# GoodBoy_V1_nRF9160dk_button_and_leds.net
KiCad netlist of a schematic drawn in Altium Designer
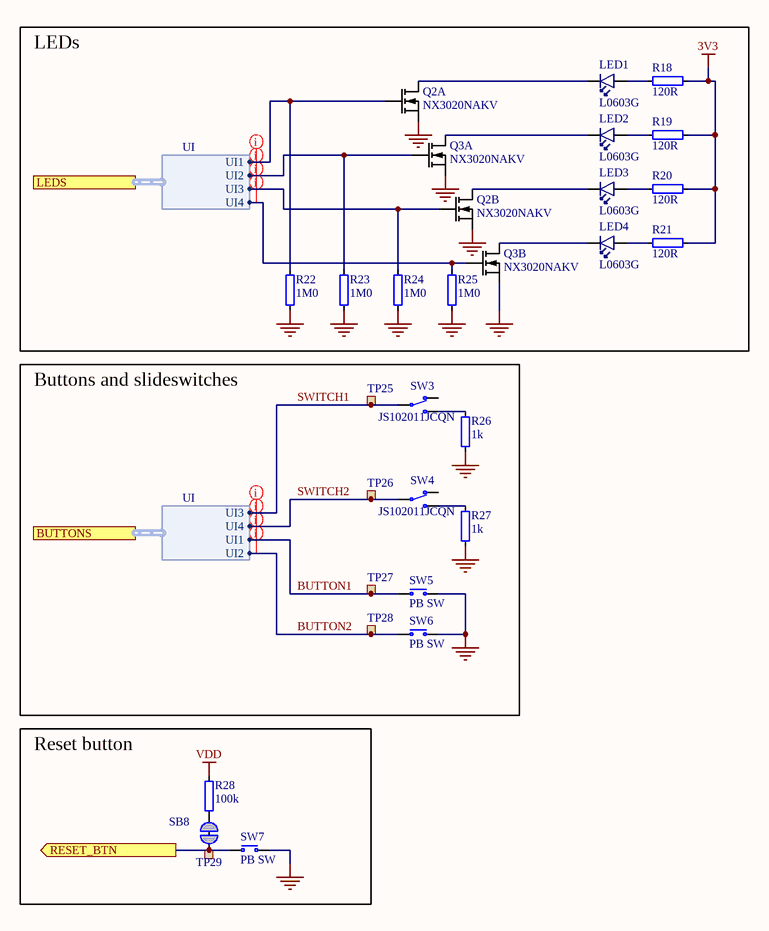
[diagram p0: GoodBoy_V1_nRF9160dk_button_and_leds.SchDoc]

(export (version "E")
  (design (tool "Eeschema 10.0.6"))
  (components
    (comp (ref "LED1")
      (value "L0603G")
      (footprint "LED_0603_G")
      (description "LED, Green, 0603, 570nm, Vf=1.7V, 2.24..5.6mcd, - 40 to +100°C")
      (fields
        (field (name "PART NUMBER") "LG L29K Smartled Green")
        (field (name "MANUFACTURER") "Osram")
        (field (name "PUBLISHER") "Nordic Semiconductor")
      )
      (libsource (lib "Nordic Discrete DB") (part "D{colon}LED"))
    )
    (comp (ref "LED2")
      (value "L0603G")
      (footprint "LED_0603_G")
      (description "LED, Green, 0603, 570nm, Vf=1.7V, 2.24..5.6mcd, - 40 to +100°C")
      (fields
        (field (name "PART NUMBER") "LG L29K Smartled Green")
        (field (name "MANUFACTURER") "Osram")
        (field (name "PUBLISHER") "Nordic Semiconductor")
      )
      (libsource (lib "Nordic Discrete DB") (part "D{colon}LED"))
    )
    (comp (ref "LED3")
      (value "L0603G")
      (footprint "LED_0603_G")
      (description "LED, Green, 0603, 570nm, Vf=1.7V, 2.24..5.6mcd, - 40 to +100°C")
      (fields
        (field (name "PART NUMBER") "LG L29K Smartled Green")
        (field (name "MANUFACTURER") "Osram")
        (field (name "PUBLISHER") "Nordic Semiconductor")
      )
      (libsource (lib "Nordic Discrete DB") (part "D{colon}LED"))
    )
    (comp (ref "LED4")
      (value "L0603G")
      (footprint "LED_0603_G")
      (description "LED, Green, 0603, 570nm, Vf=1.7V, 2.24..5.6mcd, - 40 to +100°C")
      (fields
        (field (name "PART NUMBER") "LG L29K Smartled Green")
        (field (name "MANUFACTURER") "Osram")
        (field (name "PUBLISHER") "Nordic Semiconductor")
      )
      (libsource (lib "Nordic Discrete DB") (part "D{colon}LED"))
    )
    (comp (ref "Q2")
      (value "NX3020NAKV")
      (footprint "NX3020NAKV")
      (description "MOSFET 2N-CH 30V 0.2A SOT666")
      (fields
        (field (name "MANUFACTURER") "Nexperia")
        (field (name "MANUFACTURER PART NUMBER") "NX3020NAKV,115")
        (field (name "PUBLISHER") "Nordic Semiconductor")
      )
      (libsource (lib "Nordic Discrete DB") (part "T{colon}FET-N-DUAL"))
    )
    (comp (ref "Q3")
      (value "NX3020NAKV")
      (footprint "NX3020NAKV")
      (description "MOSFET 2N-CH 30V 0.2A SOT666")
      (fields
        (field (name "MANUFACTURER") "Nexperia")
        (field (name "MANUFACTURER PART NUMBER") "NX3020NAKV,115")
        (field (name "PUBLISHER") "Nordic Semiconductor")
      )
      (libsource (lib "Nordic Discrete DB") (part "T{colon}FET-N-DUAL"))
    )
    (comp (ref "R18")
      (value "120R")
      (footprint "RESC0603X03L_C")
      (description "Resistor, ±1%, 0.05W")
      (fields (field (name "PART NUMBER") "R0201-120") (field (name "PUBLISHER") "Nordic Semiconductor"))
      (libsource (lib "Nordic Passive DB") (part "RES_1"))
    )
    (comp (ref "R19")
      (value "120R")
      (footprint "RESC0603X03L_C")
      (description "Resistor, ±1%, 0.05W")
      (fields (field (name "PART NUMBER") "R0201-120") (field (name "PUBLISHER") "Nordic Semiconductor"))
      (libsource (lib "Nordic Passive DB") (part "RES_1"))
    )
    (comp (ref "R20")
      (value "120R")
      (footprint "RESC0603X03L_C")
      (description "Resistor, ±1%, 0.05W")
      (fields (field (name "PART NUMBER") "R0201-120") (field (name "PUBLISHER") "Nordic Semiconductor"))
      (libsource (lib "Nordic Passive DB") (part "RES_1"))
    )
    (comp (ref "R21")
      (value "120R")
      (footprint "RESC0603X03L_C")
      (description "Resistor, ±1%, 0.05W")
      (fields (field (name "PART NUMBER") "R0201-120") (field (name "PUBLISHER") "Nordic Semiconductor"))
      (libsource (lib "Nordic Passive DB") (part "RES_1"))
    )
    (comp (ref "R22")
      (value "1M0")
      (footprint "RESC0603X03L_C")
      (description "Resistor, ±1%, 0.05W")
      (fields (field (name "PART NUMBER") "R0201-1M0") (field (name "PUBLISHER") "Nordic Semiconductor"))
      (libsource (lib "Nordic Passive DB") (part "RES_1"))
    )
    (comp (ref "R23")
      (value "1M0")
      (footprint "RESC0603X03L_C")
      (description "Resistor, ±1%, 0.05W")
      (fields (field (name "PART NUMBER") "R0201-1M0") (field (name "PUBLISHER") "Nordic Semiconductor"))
      (libsource (lib "Nordic Passive DB") (part "RES_1"))
    )
    (comp (ref "R24")
      (value "1M0")
      (footprint "RESC0603X03L_C")
      (description "Resistor, ±1%, 0.05W")
      (fields (field (name "PART NUMBER") "R0201-1M0") (field (name "PUBLISHER") "Nordic Semiconductor"))
      (libsource (lib "Nordic Passive DB") (part "RES_1"))
    )
    (comp (ref "R25")
      (value "1M0")
      (footprint "RESC0603X03L_C")
      (description "Resistor, ±1%, 0.05W")
      (fields (field (name "PART NUMBER") "R0201-1M0") (field (name "PUBLISHER") "Nordic Semiconductor"))
      (libsource (lib "Nordic Passive DB") (part "RES_1"))
    )
    (comp (ref "R26")
      (value "1k")
      (footprint "RESC0603X03L_C")
      (description "Resistor, ±1%, 0.05W")
      (fields (field (name "PART NUMBER") "R0201-1k0") (field (name "PUBLISHER") "Nordic Semiconductor"))
      (libsource (lib "Nordic Passive DB") (part "RES_1"))
    )
    (comp (ref "R27")
      (value "1k")
      (footprint "RESC0603X03L_C")
      (description "Resistor, ±1%, 0.05W")
      (fields (field (name "PART NUMBER") "R0201-1k0") (field (name "PUBLISHER") "Nordic Semiconductor"))
      (libsource (lib "Nordic Passive DB") (part "RES_1"))
    )
    (comp (ref "R28")
      (value "100k")
      (footprint "RESC0603X03L_C")
      (description "Resistor, ±1%, 0.05W")
      (fields (field (name "PART NUMBER") "R0201-100k") (field (name "PUBLISHER") "Nordic Semiconductor"))
      (libsource (lib "Nordic Passive DB") (part "RES_1"))
    )
    (comp (ref "SB8")
      (value "Solderbridge")
      (footprint "Solderbridge_Shorted")
      (description "Shorted Solderbridge")
      (fields
        (field (name "PART NUMBER") "Solderbridge Shorted")
        (field (name "PUBLISHER") "Nordic Semiconductor")
      )
      (libsource (lib "Nordic Passive DB") (part "SOLDERBRIDGE_SHORTED"))
    )
    (comp (ref "SW3")
      (value "JS102011JCQN")
      (footprint "JS102011JCQN")
      (description "SWITCH SLIDE SPDT 300MA 6V")
      (fields
        (field (name "MANUFACTURER") "C&K Components")
        (field (name "PUBLISHER") "Nordic Semiconductor")
      )
      (libsource (lib "Nordic Discrete DB") (part "SW-SPDT"))
    )
    (comp (ref "SW4")
      (value "JS102011JCQN")
      (footprint "JS102011JCQN")
      (description "SWITCH SLIDE SPDT 300MA 6V")
      (fields
        (field (name "MANUFACTURER") "C&K Components")
        (field (name "PUBLISHER") "Nordic Semiconductor")
      )
      (libsource (lib "Nordic Discrete DB") (part "SW-SPDT"))
    )
    (comp (ref "SW5")
      (value "PB SW")
      (footprint "Switch-PB-6.2x6.3mm-SMD")
      (description "Tactile Switch, SPNO, SMD, 160gf, 6.2x6.3x2.5mm")
      (fields
        (field (name "PART NUMBER") "Switch-PB-6.2x6.3mm-SMD")
        (field (name "MANUFACTURER") "Dailywell")
        (field (name "PUBLISHER") "Nordic Semiconductor")
      )
      (libsource (lib "Nordic Discrete DB") (part "SW-PB"))
    )
    (comp (ref "SW6")
      (value "PB SW")
      (footprint "Switch-PB-6.2x6.3mm-SMD")
      (description "Tactile Switch, SPNO, SMD, 160gf, 6.2x6.3x2.5mm")
      (fields
        (field (name "PART NUMBER") "Switch-PB-6.2x6.3mm-SMD")
        (field (name "MANUFACTURER") "Dailywell")
        (field (name "PUBLISHER") "Nordic Semiconductor")
      )
      (libsource (lib "Nordic Discrete DB") (part "SW-PB"))
    )
    (comp (ref "SW7")
      (value "PB SW")
      (footprint "Switch-PB-6.2x6.3mm-SMD")
      (description "Tactile Switch, SPNO, SMD, 160gf, 6.2x6.3x2.5mm")
      (fields
        (field (name "PART NUMBER") "Switch-PB-6.2x6.3mm-SMD")
        (field (name "MANUFACTURER") "Dailywell")
        (field (name "PUBLISHER") "Nordic Semiconductor")
      )
      (libsource (lib "Nordic Discrete DB") (part "SW-PB"))
    )
    (comp (ref "TP25")
      (value "Ø1.5mm,SMD")
      (footprint "TP_SMD_Ø1.5mm")
      (description "1.0mm circular SMD testpad")
      (fields
        (field (name "PART NUMBER") "TP_SMD_Ø1.5MM")
        (field (name "MANUFACTURER") "Nordic Semiconductor")
        (field (name "PUBLISHER") "Nordic Semiconductor")
      )
      (libsource (lib "Nordic Passive DB") (part "TESTPAD"))
    )
    (comp (ref "TP26")
      (value "Ø1.5mm,SMD")
      (footprint "TP_SMD_Ø1.5mm")
      (description "1.0mm circular SMD testpad")
      (fields
        (field (name "PART NUMBER") "TP_SMD_Ø1.5MM")
        (field (name "MANUFACTURER") "Nordic Semiconductor")
        (field (name "PUBLISHER") "Nordic Semiconductor")
      )
      (libsource (lib "Nordic Passive DB") (part "TESTPAD"))
    )
    (comp (ref "TP27")
      (value "Ø1.5mm,SMD")
      (footprint "TP_SMD_Ø1.5mm")
      (description "1.0mm circular SMD testpad")
      (fields
        (field (name "PART NUMBER") "TP_SMD_Ø1.5MM")
        (field (name "MANUFACTURER") "Nordic Semiconductor")
        (field (name "PUBLISHER") "Nordic Semiconductor")
      )
      (libsource (lib "Nordic Passive DB") (part "TESTPAD"))
    )
    (comp (ref "TP28")
      (value "Ø1.5mm,SMD")
      (footprint "TP_SMD_Ø1.5mm")
      (description "1.0mm circular SMD testpad")
      (fields
        (field (name "PART NUMBER") "TP_SMD_Ø1.5MM")
        (field (name "MANUFACTURER") "Nordic Semiconductor")
        (field (name "PUBLISHER") "Nordic Semiconductor")
      )
      (libsource (lib "Nordic Passive DB") (part "TESTPAD"))
    )
    (comp (ref "TP29")
      (value "Ø1.5mm,SMD")
      (footprint "TP_SMD_Ø1.5mm")
      (description "1.0mm circular SMD testpad")
      (fields
        (field (name "PART NUMBER") "TP_SMD_Ø1.5MM")
        (field (name "MANUFACTURER") "Nordic Semiconductor")
        (field (name "PUBLISHER") "Nordic Semiconductor")
      )
      (libsource (lib "") (part "TESTPAD_1"))
    )
  )
  (nets
    (net (code "2") (name "/BUTTON1") (class "Default")
      (node (ref "SW5") (pin "2") (pinfunction "COM_2") (pintype "passive"))
      (node (ref "TP27") (pin "1") (pinfunction "1_1") (pintype "passive"))
    )
    (net (code "3") (name "/BUTTON2") (class "Default")
      (node (ref "SW6") (pin "2") (pinfunction "COM_2") (pintype "passive"))
      (node (ref "TP28") (pin "1") (pinfunction "1_1") (pintype "passive"))
    )
    (net (code "4") (name "/RESET_BTN") (class "Default")
      (node (ref "SB8") (pin "1") (pinfunction "0_1") (pintype "passive"))
      (node (ref "SW7") (pin "2") (pinfunction "COM_2") (pintype "passive"))
      (node (ref "TP29") (pin "1") (pinfunction "1_1") (pintype "passive"))
    )
    (net (code "5") (name "/SWITCH1") (class "Default")
      (node (ref "SW3") (pin "2") (pinfunction "COM_2") (pintype "passive"))
      (node (ref "TP25") (pin "1") (pinfunction "1_1") (pintype "passive"))
    )
    (net (code "6") (name "/SWITCH2") (class "Default")
      (node (ref "SW4") (pin "2") (pinfunction "COM_2") (pintype "passive"))
      (node (ref "TP26") (pin "1") (pinfunction "1_1") (pintype "passive"))
    )
    (net (code "8") (name "3V3") (class "Default")
      (node (ref "R18") (pin "2") (pinfunction "2_2") (pintype "passive"))
      (node (ref "R19") (pin "2") (pinfunction "2_2") (pintype "passive"))
      (node (ref "R20") (pin "2") (pinfunction "2_2") (pintype "passive"))
      (node (ref "R21") (pin "2") (pinfunction "2_2") (pintype "passive"))
    )
    (net (code "9") (name "GND") (class "Default")
      (node (ref "Q2") (pin "1") (pinfunction "S1_1") (pintype "passive"))
      (node (ref "Q2") (pin "4") (pinfunction "S2_4") (pintype "passive"))
      (node (ref "Q3") (pin "1") (pinfunction "S1_1") (pintype "passive"))
      (node (ref "Q3") (pin "4") (pinfunction "S2_4") (pintype "passive"))
      (node (ref "R22") (pin "1") (pinfunction "1_1") (pintype "passive"))
      (node (ref "R23") (pin "1") (pinfunction "1_1") (pintype "passive"))
      (node (ref "R24") (pin "1") (pinfunction "1_1") (pintype "passive"))
      (node (ref "R25") (pin "1") (pinfunction "1_1") (pintype "passive"))
      (node (ref "R26") (pin "1") (pinfunction "1_1") (pintype "passive"))
      (node (ref "R27") (pin "1") (pinfunction "1_1") (pintype "passive"))
      (node (ref "SW5") (pin "1") (pinfunction "N.O_1") (pintype "passive"))
      (node (ref "SW6") (pin "1") (pinfunction "N.O_1") (pintype "passive"))
      (node (ref "SW7") (pin "1") (pinfunction "N.O_1") (pintype "passive"))
    )
    (net (code "10") (name "Net-(LED1-A)") (class "Default")
      (node (ref "LED1") (pin "2") (pinfunction "A_2") (pintype "passive"))
      (node (ref "R18") (pin "1") (pinfunction "1_1") (pintype "passive"))
    )
    (net (code "11") (name "Net-(LED1-C)") (class "Default")
      (node (ref "LED1") (pin "1") (pinfunction "C_1") (pintype "passive"))
      (node (ref "Q2") (pin "6") (pinfunction "D1_6") (pintype "passive"))
    )
    (net (code "12") (name "Net-(LED2-A)") (class "Default")
      (node (ref "LED2") (pin "2") (pinfunction "A_2") (pintype "passive"))
      (node (ref "R19") (pin "1") (pinfunction "1_1") (pintype "passive"))
    )
    (net (code "13") (name "Net-(LED2-C)") (class "Default")
      (node (ref "LED2") (pin "1") (pinfunction "C_1") (pintype "passive"))
      (node (ref "Q3") (pin "6") (pinfunction "D1_6") (pintype "passive"))
    )
    (net (code "14") (name "Net-(LED3-A)") (class "Default")
      (node (ref "LED3") (pin "2") (pinfunction "A_2") (pintype "passive"))
      (node (ref "R20") (pin "1") (pinfunction "1_1") (pintype "passive"))
    )
    (net (code "15") (name "Net-(LED3-C)") (class "Default")
      (node (ref "LED3") (pin "1") (pinfunction "C_1") (pintype "passive"))
      (node (ref "Q2") (pin "3") (pinfunction "D2_3") (pintype "passive"))
    )
    (net (code "16") (name "Net-(LED4-A)") (class "Default")
      (node (ref "LED4") (pin "2") (pinfunction "A_2") (pintype "passive"))
      (node (ref "R21") (pin "1") (pinfunction "1_1") (pintype "passive"))
    )
    (net (code "17") (name "Net-(LED4-C)") (class "Default")
      (node (ref "LED4") (pin "1") (pinfunction "C_1") (pintype "passive"))
      (node (ref "Q3") (pin "3") (pinfunction "D2_3") (pintype "passive"))
    )
    (net (code "18") (name "Net-(Q2A-G1)") (class "Default")
      (node (ref "Q2") (pin "2") (pinfunction "G1_2") (pintype "passive"))
      (node (ref "R22") (pin "2") (pinfunction "2_2") (pintype "passive"))
    )
    (net (code "19") (name "Net-(Q2B-G2)") (class "Default")
      (node (ref "Q2") (pin "5") (pinfunction "G2_5") (pintype "passive"))
      (node (ref "R24") (pin "2") (pinfunction "2_2") (pintype "passive"))
    )
    (net (code "20") (name "Net-(Q3A-G1)") (class "Default")
      (node (ref "Q3") (pin "2") (pinfunction "G1_2") (pintype "passive"))
      (node (ref "R23") (pin "2") (pinfunction "2_2") (pintype "passive"))
    )
    (net (code "21") (name "Net-(Q3B-G2)") (class "Default")
      (node (ref "Q3") (pin "5") (pinfunction "G2_5") (pintype "passive"))
      (node (ref "R25") (pin "2") (pinfunction "2_2") (pintype "passive"))
    )
    (net (code "22") (name "Net-(SB8-1)") (class "Default")
      (node (ref "R28") (pin "1") (pinfunction "1_1") (pintype "passive"))
      (node (ref "SB8") (pin "2") (pinfunction "1_2") (pintype "passive"))
    )
    (net (code "23") (name "Net-(SW3-N.O)") (class "Default")
      (node (ref "R26") (pin "2") (pinfunction "2_2") (pintype "passive"))
      (node (ref "SW3") (pin "3") (pinfunction "N.O_3") (pintype "passive"))
    )
    (net (code "24") (name "Net-(SW4-N.O)") (class "Default")
      (node (ref "R27") (pin "2") (pinfunction "2_2") (pintype "passive"))
      (node (ref "SW4") (pin "3") (pinfunction "N.O_3") (pintype "passive"))
    )
    (net (code "25") (name "VDD") (class "Default")
      (node (ref "R28") (pin "2") (pinfunction "2_2") (pintype "passive"))
    )
    (net (code "26") (name "unconnected-(SW3-N.C-Pad1)") (class "Default")
      (node (ref "SW3") (pin "1") (pinfunction "N.C_1") (pintype "passive"))
    )
    (net (code "27") (name "unconnected-(SW4-N.C-Pad1)") (class "Default")
      (node (ref "SW4") (pin "1") (pinfunction "N.C_1") (pintype "passive"))
    )
  )
)
